# FEU.net
KiCad netlist of a schematic drawn in EAGLE
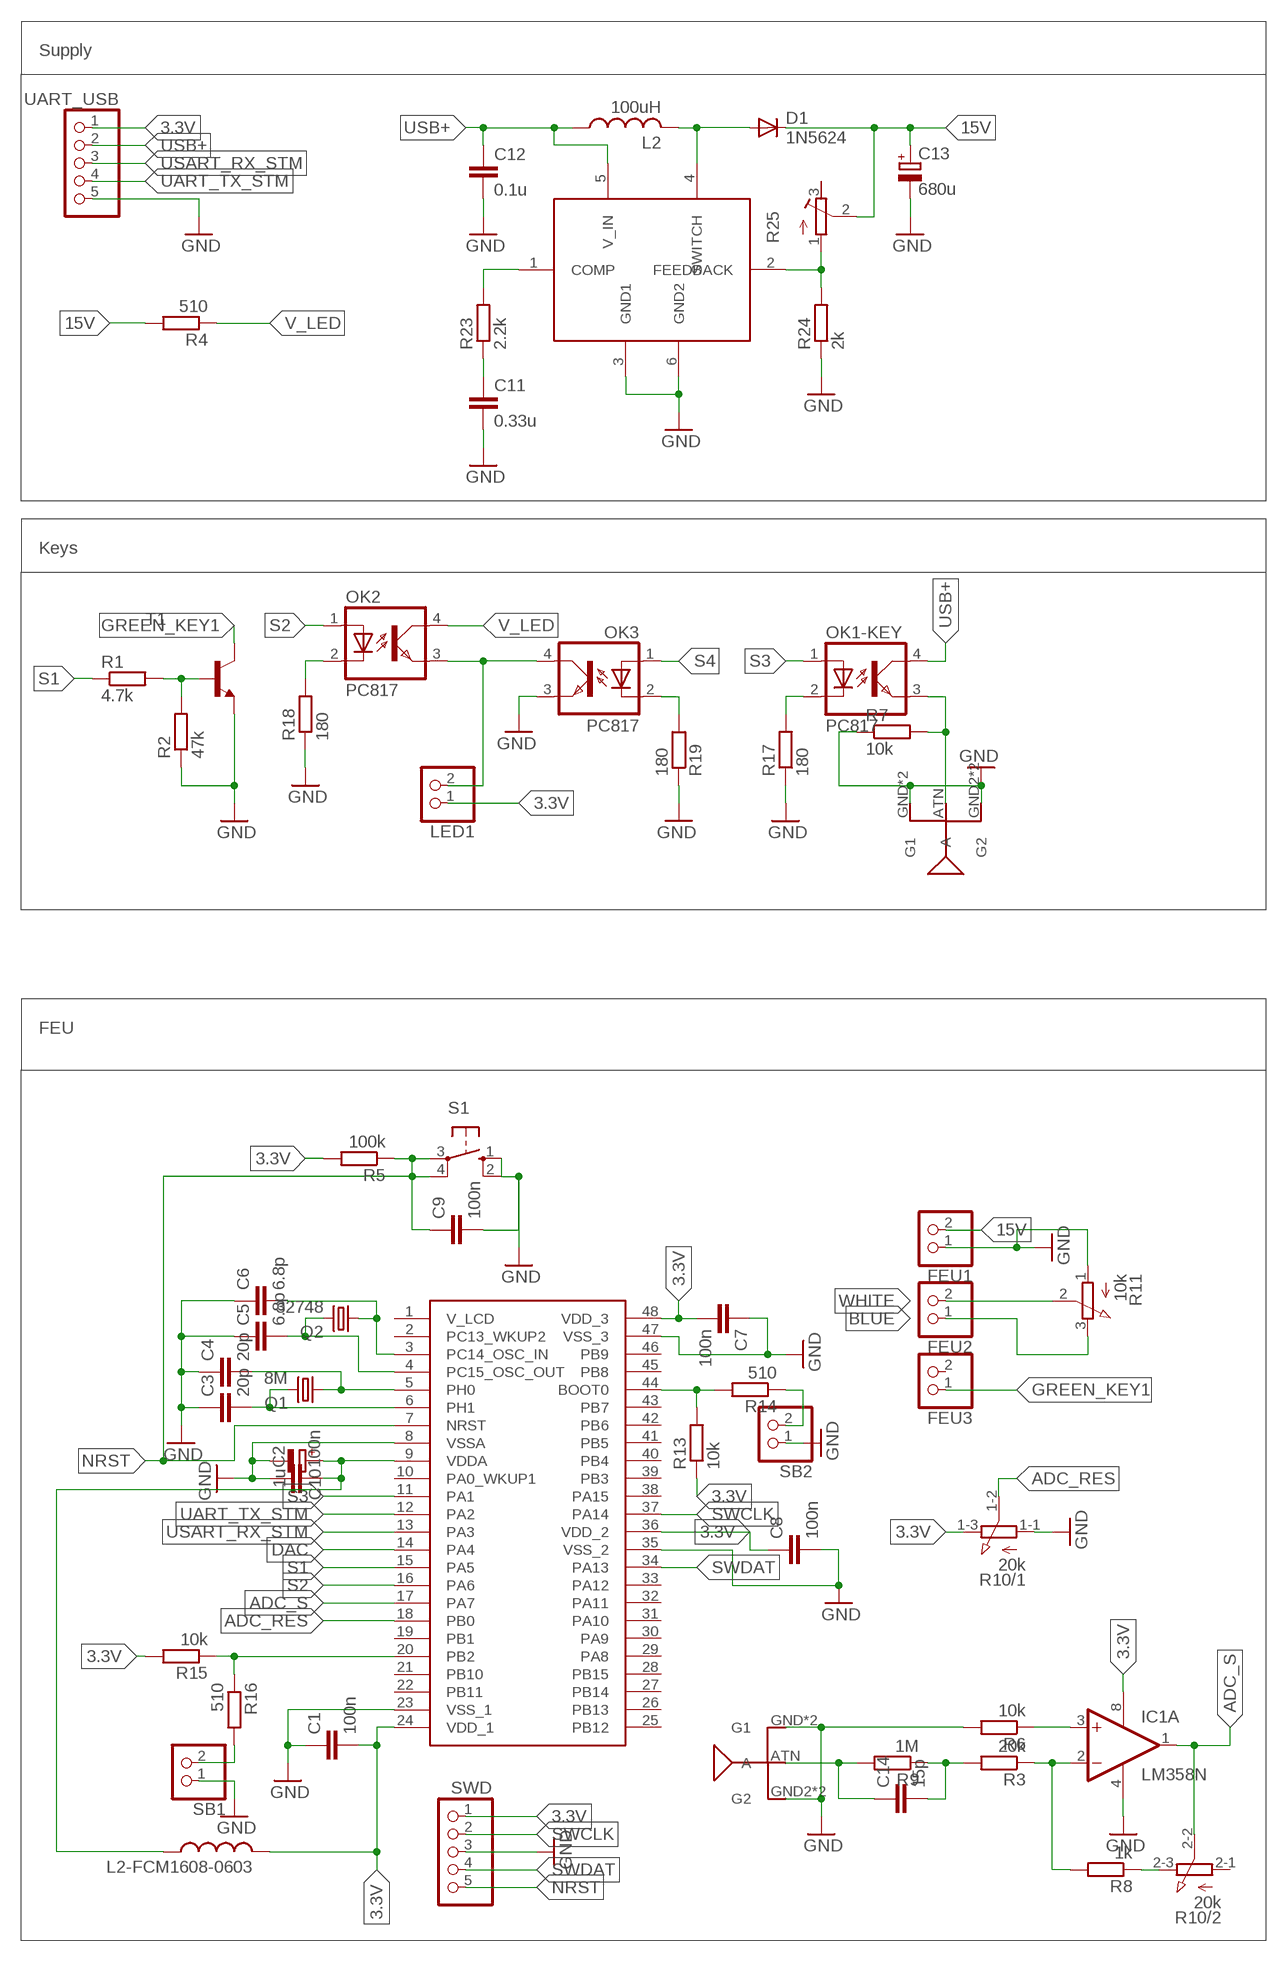
[diagram p0: schematic, sheet 1]

(export (version "E")
  (design (tool "Eeschema 10.0.6"))
  (components
    (comp (ref "C1")
      (value "100n")
      (footprint "eagle-import:C0805")
      (libsource (lib "eagle-import") (part "C-EUC0805"))
    )
    (comp (ref "C2")
      (value "100n")
      (footprint "eagle-import:C0805")
      (libsource (lib "eagle-import") (part "C-EUC0805"))
    )
    (comp (ref "C3")
      (value "20p")
      (footprint "eagle-import:C0805")
      (libsource (lib "eagle-import") (part "C-EUC0805"))
    )
    (comp (ref "C4")
      (value "20p")
      (footprint "eagle-import:C0805")
      (libsource (lib "eagle-import") (part "C-EUC0805"))
    )
    (comp (ref "C5")
      (value "6.8p")
      (footprint "eagle-import:C0805")
      (libsource (lib "eagle-import") (part "C-EUC0805"))
    )
    (comp (ref "C6")
      (value "6.8p")
      (footprint "eagle-import:C0805")
      (libsource (lib "eagle-import") (part "C-EUC0805"))
    )
    (comp (ref "C7")
      (value "100n")
      (footprint "eagle-import:C0805")
      (libsource (lib "eagle-import") (part "C-EUC0805"))
    )
    (comp (ref "C8")
      (value "100n")
      (footprint "eagle-import:C0805")
      (libsource (lib "eagle-import") (part "C-EUC0805"))
    )
    (comp (ref "C9")
      (value "100n")
      (footprint "eagle-import:C0805")
      (libsource (lib "eagle-import") (part "C-EUC0805"))
    )
    (comp (ref "C10")
      (value "1u")
      (footprint "eagle-import:A_3216-18W")
      (libsource (lib "eagle-import") (part "CPOL-EUA/3216-18W"))
    )
    (comp (ref "C11")
      (value "0.33u")
      (footprint "eagle-import:C0805")
      (libsource (lib "eagle-import") (part "C-EUC0805"))
    )
    (comp (ref "C12")
      (value "0.1u")
      (footprint "eagle-import:C0805")
      (libsource (lib "eagle-import") (part "C-EUC0805"))
    )
    (comp (ref "C13")
      (value "680u")
      (footprint "eagle-import:E5-5")
      (libsource (lib "eagle-import") (part "CPOL-EUE5-5"))
    )
    (comp (ref "C14")
      (value "15p")
      (footprint "eagle-import:C0805")
      (libsource (lib "eagle-import") (part "C-EUC0805"))
    )
    (comp (ref "D1")
      (value "1N5624")
      (footprint "eagle-import:DO201-15")
      (libsource (lib "eagle-import") (part "1N5624"))
    )
    (comp (ref "FEU1")
      (value "PINHD-1X2")
      (footprint "eagle-import:1X02")
      (libsource (lib "eagle-import") (part "PINHD-1X2"))
    )
    (comp (ref "FEU2")
      (value "PINHD-1X2")
      (footprint "eagle-import:1X02")
      (libsource (lib "eagle-import") (part "PINHD-1X2"))
    )
    (comp (ref "FEU3")
      (value "PINHD-1X2")
      (footprint "eagle-import:1X02")
      (libsource (lib "eagle-import") (part "PINHD-1X2"))
    )
    (comp (ref "IC1")
      (value "LM358N")
      (footprint "eagle-import:DIL08")
      (libsource (lib "eagle-import") (part "LM358N"))
    )
    (comp (ref "L2")
      (value "100uH")
      (footprint "eagle-import:0207_5V")
      (libsource (lib "eagle-import") (part "L-US0207/5V"))
    )
    (comp (ref "L2-FCM1608-0603")
      (value "L-USL3216C")
      (footprint "eagle-import:L3216C")
      (libsource (lib "eagle-import") (part "L-USL3216C"))
    )
    (comp (ref "LED1")
      (value "PINHD-1X2")
      (footprint "eagle-import:1X02")
      (libsource (lib "eagle-import") (part "PINHD-1X2"))
    )
    (comp (ref "OK1-KEY")
      (value "PC817")
      (footprint "eagle-import:DIL04")
      (fields (field (name "MPN") "PC817X4J000F"))
      (libsource (lib "eagle-import") (part "PC817"))
    )
    (comp (ref "OK2")
      (value "PC817")
      (footprint "eagle-import:DIL04")
      (fields (field (name "MPN") "PC817X4J000F"))
      (libsource (lib "eagle-import") (part "PC817"))
    )
    (comp (ref "OK3")
      (value "PC817")
      (footprint "eagle-import:DIL04")
      (fields (field (name "MPN") "PC817X4J000F"))
      (libsource (lib "eagle-import") (part "PC817"))
    )
    (comp (ref "Q1")
      (value "8M")
      (footprint "eagle-import:HC49_S")
      (fields (field (name "OC_FARNELL") "1667008"))
      (libsource (lib "eagle-import") (part "CRYSTALHC49S"))
    )
    (comp (ref "Q2")
      (value "32748")
      (footprint "eagle-import:TC26H")
      (libsource (lib "eagle-import") (part "CRYSTALTC26H"))
    )
    (comp (ref "R1")
      (value "4.7k")
      (footprint "eagle-import:R0805")
      (libsource (lib "eagle-import") (part "R-EU_R0805"))
    )
    (comp (ref "R2")
      (value "47k")
      (footprint "eagle-import:R0805")
      (libsource (lib "eagle-import") (part "R-EU_R0805"))
    )
    (comp (ref "R3")
      (value "20k")
      (footprint "eagle-import:M1206")
      (libsource (lib "eagle-import") (part "R-EU_M1206"))
    )
    (comp (ref "R4")
      (value "510")
      (footprint "eagle-import:R0805")
      (libsource (lib "eagle-import") (part "R-EU_R0805"))
    )
    (comp (ref "R5")
      (value "100k")
      (footprint "eagle-import:R0805")
      (libsource (lib "eagle-import") (part "R-EU_R0805"))
    )
    (comp (ref "R6")
      (value "10k")
      (footprint "eagle-import:M1206")
      (libsource (lib "eagle-import") (part "R-EU_M1206"))
    )
    (comp (ref "R7")
      (value "10k")
      (footprint "eagle-import:R0805")
      (libsource (lib "eagle-import") (part "R-EU_R0805"))
    )
    (comp (ref "R8")
      (value "1k")
      (footprint "eagle-import:M1206")
      (libsource (lib "eagle-import") (part "R-EU_M1206"))
    )
    (comp (ref "R9")
      (value "1M")
      (footprint "eagle-import:M1206")
      (libsource (lib "eagle-import") (part "R-EU_M1206"))
    )
    (comp (ref "R10")
      (value "20k")
      (footprint "eagle-import:3RP_1610G")
      (libsource (lib "eagle-import") (part "3RP/1610G"))
    )
    (comp (ref "R11")
      (value "10k")
      (footprint "eagle-import:3RP_1610N")
      (libsource (lib "eagle-import") (part "3RP/1610N"))
    )
    (comp (ref "R13")
      (value "10k")
      (footprint "eagle-import:R0805")
      (libsource (lib "eagle-import") (part "R-EU_R0805"))
    )
    (comp (ref "R14")
      (value "510")
      (footprint "eagle-import:R0805")
      (libsource (lib "eagle-import") (part "R-EU_R0805"))
    )
    (comp (ref "R15")
      (value "10k")
      (footprint "eagle-import:R0805")
      (libsource (lib "eagle-import") (part "R-EU_R0805"))
    )
    (comp (ref "R16")
      (value "510")
      (footprint "eagle-import:R0805")
      (libsource (lib "eagle-import") (part "R-EU_R0805"))
    )
    (comp (ref "R17")
      (value "180")
      (footprint "eagle-import:R0805")
      (libsource (lib "eagle-import") (part "R-EU_R0805"))
    )
    (comp (ref "R18")
      (value "180")
      (footprint "eagle-import:R0805")
      (libsource (lib "eagle-import") (part "R-EU_R0805"))
    )
    (comp (ref "R19")
      (value "180")
      (footprint "eagle-import:R0805")
      (libsource (lib "eagle-import") (part "R-EU_R0805"))
    )
    (comp (ref "R23")
      (value "2.2k")
      (footprint "eagle-import:R0805")
      (libsource (lib "eagle-import") (part "R-EU_R0805"))
    )
    (comp (ref "R24")
      (value "2k")
      (footprint "eagle-import:R0805")
      (libsource (lib "eagle-import") (part "R-EU_R0805"))
    )
    (comp (ref "R25")
      (value "R-TRIMM3339P")
      (footprint "eagle-import:RTRIM3339P")
      (libsource (lib "eagle-import") (part "R-TRIMM3339P"))
    )
    (comp (ref "S1")
      (value "10-XX")
      (footprint "eagle-import:B3F-10XX")
      (fields (field (name "MPN") "B3F-1000"))
      (libsource (lib "eagle-import") (part "10-XX"))
    )
    (comp (ref "SB1")
      (value "PINHD-1X2")
      (footprint "eagle-import:1X02")
      (libsource (lib "eagle-import") (part "PINHD-1X2"))
    )
    (comp (ref "SB2")
      (value "PINHD-1X2")
      (footprint "eagle-import:1X02")
      (libsource (lib "eagle-import") (part "PINHD-1X2"))
    )
    (comp (ref "SWD")
      (value "PINHD-1X5")
      (footprint "eagle-import:1X05")
      (libsource (lib "eagle-import") (part "PINHD-1X5"))
    )
    (comp (ref "T1")
      (value "BC846B-NPN-SOT23-BEC")
      (footprint "eagle-import:SOT23-BEC")
      (libsource (lib "eagle-import") (part "-NPN-SOT23-BECBC846B"))
    )
    (comp (ref "U$1")
      (value "STM32L152C6")
      (footprint "eagle-import:LQFP48")
      (libsource (lib "eagle-import") (part "STM32L152C6"))
    )
    (comp (ref "U$2")
      (value "GSM_ANT")
      (footprint "eagle-import:GSM")
      (libsource (lib "eagle-import") (part "GSM_ANT"))
    )
    (comp (ref "U$3")
      (value "GSM_ANT")
      (footprint "eagle-import:GSM")
      (libsource (lib "eagle-import") (part "GSM_ANT"))
    )
    (comp (ref "U$4")
      (value "LM2577")
      (footprint "eagle-import:TO263-5")
      (libsource (lib "eagle-import") (part "LM2577"))
    )
    (comp (ref "UART_USB")
      (value "PINHD-1X5")
      (footprint "eagle-import:1X05")
      (libsource (lib "eagle-import") (part "PINHD-1X5"))
    )
  )
  (nets
    (net (code "1") (name "3.3V") (class "Default")
      (node (ref "C1") (pin "2") (pinfunction "2_2") (pintype "passive"))
      (node (ref "C7") (pin "2") (pinfunction "2_2") (pintype "passive"))
      (node (ref "C8") (pin "1") (pinfunction "1_1") (pintype "passive"))
      (node (ref "IC1") (pin "8") (pinfunction "V+_8") (pintype "power_in"))
      (node (ref "L2-FCM1608-0603") (pin "2") (pinfunction "2_2") (pintype "passive"))
      (node (ref "LED1") (pin "1") (pinfunction "1_1") (pintype "passive"))
      (node (ref "R10") (pin "1-3") (pinfunction "E_1-3") (pintype "passive"))
      (node (ref "R13") (pin "1") (pinfunction "1_1") (pintype "passive"))
      (node (ref "R15") (pin "2") (pinfunction "2_2") (pintype "passive"))
      (node (ref "R5") (pin "2") (pinfunction "2_2") (pintype "passive"))
      (node (ref "SWD") (pin "1") (pinfunction "1_1") (pintype "passive"))
      (node (ref "U$1") (pin "24") (pinfunction "VDD_1_24") (pintype "bidirectional"))
      (node (ref "U$1") (pin "36") (pinfunction "VDD_2_36") (pintype "bidirectional"))
      (node (ref "U$1") (pin "48") (pinfunction "VDD_3_48") (pintype "bidirectional"))
      (node (ref "UART_USB") (pin "1") (pinfunction "1_1") (pintype "passive"))
    )
    (net (code "2") (name "15V") (class "Default")
      (node (ref "C13") (pin "+") (pinfunction "+_+") (pintype "passive"))
      (node (ref "D1") (pin "C") (pinfunction "C_C") (pintype "passive"))
      (node (ref "FEU1") (pin "2") (pinfunction "2_2") (pintype "passive"))
      (node (ref "R25") (pin "2") (pinfunction "S_2") (pintype "passive"))
      (node (ref "R4") (pin "2") (pinfunction "2_2") (pintype "passive"))
    )
    (net (code "3") (name "ADC_RES") (class "Default")
      (node (ref "R10") (pin "1-2") (pinfunction "S_1-2") (pintype "passive"))
      (node (ref "U$1") (pin "18") (pinfunction "PB0_18") (pintype "bidirectional"))
    )
    (net (code "4") (name "ADC_S") (class "Default")
      (node (ref "IC1") (pin "1") (pinfunction "OUT_1") (pintype "output"))
      (node (ref "R10") (pin "2-2") (pinfunction "S_2-2") (pintype "passive"))
      (node (ref "U$1") (pin "17") (pinfunction "PA7_17") (pintype "bidirectional"))
    )
    (net (code "5") (name "BLUE") (class "Default")
      (node (ref "FEU2") (pin "1") (pinfunction "1_1") (pintype "passive"))
      (node (ref "R11") (pin "3") (pinfunction "E_3") (pintype "passive"))
    )
    (net (code "6") (name "DAC") (class "Default")
      (node (ref "U$1") (pin "14") (pinfunction "PA4_14") (pintype "bidirectional"))
    )
    (net (code "7") (name "GND") (class "Default")
      (node (ref "C1") (pin "1") (pinfunction "1_1") (pintype "passive"))
      (node (ref "C10") (pin "-") (pinfunction "-_-") (pintype "passive"))
      (node (ref "C11") (pin "2") (pinfunction "2_2") (pintype "passive"))
      (node (ref "C12") (pin "2") (pinfunction "2_2") (pintype "passive"))
      (node (ref "C13") (pin "-") (pinfunction "-_-") (pintype "passive"))
      (node (ref "C2") (pin "1") (pinfunction "1_1") (pintype "passive"))
      (node (ref "C3") (pin "1") (pinfunction "1_1") (pintype "passive"))
      (node (ref "C4") (pin "1") (pinfunction "1_1") (pintype "passive"))
      (node (ref "C5") (pin "1") (pinfunction "1_1") (pintype "passive"))
      (node (ref "C6") (pin "1") (pinfunction "1_1") (pintype "passive"))
      (node (ref "C7") (pin "1") (pinfunction "1_1") (pintype "passive"))
      (node (ref "C8") (pin "2") (pinfunction "2_2") (pintype "passive"))
      (node (ref "C9") (pin "2") (pinfunction "2_2") (pintype "passive"))
      (node (ref "FEU1") (pin "1") (pinfunction "1_1") (pintype "passive"))
      (node (ref "IC1") (pin "4") (pinfunction "V-_4") (pintype "power_in"))
      (node (ref "OK3") (pin "3") (pinfunction "EMIT_3") (pintype "passive"))
      (node (ref "R10") (pin "1-1") (pinfunction "A_1-1") (pintype "passive"))
      (node (ref "R11") (pin "1") (pinfunction "A_1") (pintype "passive"))
      (node (ref "R17") (pin "1") (pinfunction "1_1") (pintype "passive"))
      (node (ref "R18") (pin "1") (pinfunction "1_1") (pintype "passive"))
      (node (ref "R19") (pin "1") (pinfunction "1_1") (pintype "passive"))
      (node (ref "R2") (pin "1") (pinfunction "1_1") (pintype "passive"))
      (node (ref "R24") (pin "1") (pinfunction "1_1") (pintype "passive"))
      (node (ref "R6") (pin "2") (pinfunction "2_2") (pintype "passive"))
      (node (ref "R7") (pin "1") (pinfunction "1_1") (pintype "passive"))
      (node (ref "S1") (pin "1") (pinfunction "S_1") (pintype "passive"))
      (node (ref "S1") (pin "2") (pinfunction "S1_2") (pintype "passive"))
      (node (ref "SB1") (pin "1") (pinfunction "1_1") (pintype "passive"))
      (node (ref "SB2") (pin "1") (pinfunction "1_1") (pintype "passive"))
      (node (ref "SWD") (pin "3") (pinfunction "3_3") (pintype "passive"))
      (node (ref "T1") (pin "E") (pinfunction "E_E") (pintype "passive"))
      (node (ref "U$1") (pin "23") (pinfunction "VSS_1_23") (pintype "bidirectional"))
      (node (ref "U$1") (pin "35") (pinfunction "VSS_2_35") (pintype "bidirectional"))
      (node (ref "U$1") (pin "47") (pinfunction "VSS_3_47") (pintype "bidirectional"))
      (node (ref "U$1") (pin "8") (pinfunction "VSSA_8") (pintype "bidirectional"))
      (node (ref "U$2") (pin "GND") (pinfunction "G1_GND") (pintype "bidirectional"))
      (node (ref "U$2") (pin "GND1") (pinfunction "G1_GND1") (pintype "bidirectional"))
      (node (ref "U$2") (pin "GND2") (pinfunction "G2_GND2") (pintype "bidirectional"))
      (node (ref "U$2") (pin "GND3") (pinfunction "G2_GND3") (pintype "bidirectional"))
      (node (ref "U$3") (pin "GND") (pinfunction "G1_GND") (pintype "bidirectional"))
      (node (ref "U$3") (pin "GND1") (pinfunction "G1_GND1") (pintype "bidirectional"))
      (node (ref "U$3") (pin "GND2") (pinfunction "G2_GND2") (pintype "bidirectional"))
      (node (ref "U$3") (pin "GND3") (pinfunction "G2_GND3") (pintype "bidirectional"))
      (node (ref "U$4") (pin "3") (pinfunction "GND1_3") (pintype "bidirectional"))
      (node (ref "U$4") (pin "6") (pinfunction "GND2_6") (pintype "bidirectional"))
      (node (ref "UART_USB") (pin "5") (pinfunction "5_5") (pintype "passive"))
    )
    (net (code "8") (name "GREEN_KEY1") (class "Default")
      (node (ref "FEU3") (pin "1") (pinfunction "1_1") (pintype "passive"))
      (node (ref "T1") (pin "C") (pinfunction "C_C") (pintype "passive"))
    )
    (net (code "9") (name "NRST") (class "Default")
      (node (ref "C9") (pin "1") (pinfunction "1_1") (pintype "passive"))
      (node (ref "R5") (pin "1") (pinfunction "1_1") (pintype "passive"))
      (node (ref "S1") (pin "3") (pinfunction "P_3") (pintype "passive"))
      (node (ref "S1") (pin "4") (pinfunction "P1_4") (pintype "passive"))
      (node (ref "SWD") (pin "5") (pinfunction "5_5") (pintype "passive"))
      (node (ref "U$1") (pin "7") (pinfunction "NRST_7") (pintype "bidirectional"))
    )
    (net (code "10") (name "Net-(C11-Pad1)") (class "Default")
      (node (ref "C11") (pin "1") (pinfunction "1_1") (pintype "passive"))
      (node (ref "R23") (pin "1") (pinfunction "1_1") (pintype "passive"))
    )
    (net (code "11") (name "Net-(C14-Pad2)") (class "Default")
      (node (ref "C14") (pin "2") (pinfunction "2_2") (pintype "passive"))
      (node (ref "R3") (pin "2") (pinfunction "2_2") (pintype "passive"))
      (node (ref "R9") (pin "1") (pinfunction "1_1") (pintype "passive"))
    )
    (net (code "12") (name "Net-(IC1A-+IN)") (class "Default")
      (node (ref "IC1") (pin "3") (pinfunction "+IN_3") (pintype "input"))
      (node (ref "R6") (pin "1") (pinfunction "1_1") (pintype "passive"))
    )
    (net (code "13") (name "Net-(IC1A--IN)") (class "Default")
      (node (ref "IC1") (pin "2") (pinfunction "-IN_2") (pintype "input"))
      (node (ref "R3") (pin "1") (pinfunction "1_1") (pintype "passive"))
      (node (ref "R8") (pin "2") (pinfunction "2_2") (pintype "passive"))
    )
    (net (code "14") (name "Net-(OK1-KEY-C)") (class "Default")
      (node (ref "OK1-KEY") (pin "2") (pinfunction "C_2") (pintype "passive"))
      (node (ref "R17") (pin "2") (pinfunction "2_2") (pintype "passive"))
    )
    (net (code "15") (name "Net-(OK1-KEY-EMIT)") (class "Default")
      (node (ref "OK1-KEY") (pin "3") (pinfunction "EMIT_3") (pintype "passive"))
      (node (ref "R7") (pin "2") (pinfunction "2_2") (pintype "passive"))
      (node (ref "U$3") (pin "ATN") (pinfunction "A_ATN") (pintype "bidirectional"))
    )
    (net (code "16") (name "Net-(OK2-C)") (class "Default")
      (node (ref "OK2") (pin "2") (pinfunction "C_2") (pintype "passive"))
      (node (ref "R18") (pin "2") (pinfunction "2_2") (pintype "passive"))
    )
    (net (code "17") (name "Net-(OK2-EMIT)") (class "Default")
      (node (ref "LED1") (pin "2") (pinfunction "2_2") (pintype "passive"))
      (node (ref "OK2") (pin "3") (pinfunction "EMIT_3") (pintype "passive"))
      (node (ref "OK3") (pin "4") (pinfunction "COL_4") (pintype "passive"))
    )
    (net (code "18") (name "Net-(OK3-C)") (class "Default")
      (node (ref "OK3") (pin "2") (pinfunction "C_2") (pintype "passive"))
      (node (ref "R19") (pin "2") (pinfunction "2_2") (pintype "passive"))
    )
    (net (code "19") (name "Net-(R1-Pad2)") (class "Default")
      (node (ref "R1") (pin "2") (pinfunction "2_2") (pintype "passive"))
      (node (ref "R2") (pin "2") (pinfunction "2_2") (pintype "passive"))
      (node (ref "T1") (pin "B") (pinfunction "B_B") (pintype "passive"))
    )
    (net (code "20") (name "Net-(R10B-E)") (class "Default")
      (node (ref "R10") (pin "2-3") (pinfunction "E_2-3") (pintype "passive"))
      (node (ref "R8") (pin "1") (pinfunction "1_1") (pintype "passive"))
    )
    (net (code "21") (name "Net-(R14-Pad1)") (class "Default")
      (node (ref "R14") (pin "1") (pinfunction "1_1") (pintype "passive"))
      (node (ref "SB2") (pin "2") (pinfunction "2_2") (pintype "passive"))
    )
    (net (code "22") (name "Net-(R16-Pad2)") (class "Default")
      (node (ref "R16") (pin "2") (pinfunction "2_2") (pintype "passive"))
      (node (ref "SB1") (pin "2") (pinfunction "2_2") (pintype "passive"))
    )
    (net (code "23") (name "Net-(R25-E)") (class "Default")
      (node (ref "R24") (pin "2") (pinfunction "2_2") (pintype "passive"))
      (node (ref "R25") (pin "1") (pinfunction "E_1") (pintype "passive"))
      (node (ref "U$4") (pin "2") (pinfunction "FEEDBACK_2") (pintype "bidirectional"))
    )
    (net (code "24") (name "Net-(U$1-BOOT0)") (class "Default")
      (node (ref "R13") (pin "2") (pinfunction "2_2") (pintype "passive"))
      (node (ref "R14") (pin "2") (pinfunction "2_2") (pintype "passive"))
      (node (ref "U$1") (pin "44") (pinfunction "BOOT0_44") (pintype "bidirectional"))
    )
    (net (code "25") (name "Net-(U$1-PB2)") (class "Default")
      (node (ref "R15") (pin "1") (pinfunction "1_1") (pintype "passive"))
      (node (ref "R16") (pin "1") (pinfunction "1_1") (pintype "passive"))
      (node (ref "U$1") (pin "20") (pinfunction "PB2_20") (pintype "bidirectional"))
    )
    (net (code "26") (name "Net-(U$1-PC14_OSC_IN)") (class "Default")
      (node (ref "C6") (pin "2") (pinfunction "2_2") (pintype "passive"))
      (node (ref "Q2") (pin "1") (pinfunction "1_1") (pintype "passive"))
      (node (ref "U$1") (pin "3") (pinfunction "PC14_OSC_IN_3") (pintype "bidirectional"))
    )
    (net (code "27") (name "Net-(U$1-PC15_OSC_OUT)") (class "Default")
      (node (ref "C5") (pin "2") (pinfunction "2_2") (pintype "passive"))
      (node (ref "Q2") (pin "2") (pinfunction "2_2") (pintype "passive"))
      (node (ref "U$1") (pin "4") (pinfunction "PC15_OSC_OUT_4") (pintype "bidirectional"))
    )
    (net (code "28") (name "Net-(U$1-PH0)") (class "Default")
      (node (ref "C4") (pin "2") (pinfunction "2_2") (pintype "passive"))
      (node (ref "Q1") (pin "1") (pinfunction "1_1") (pintype "passive"))
      (node (ref "U$1") (pin "5") (pinfunction "PH0_5") (pintype "bidirectional"))
    )
    (net (code "29") (name "Net-(U$1-PH1)") (class "Default")
      (node (ref "C3") (pin "2") (pinfunction "2_2") (pintype "passive"))
      (node (ref "Q1") (pin "2") (pinfunction "2_2") (pintype "passive"))
      (node (ref "U$1") (pin "6") (pinfunction "PH1_6") (pintype "bidirectional"))
    )
    (net (code "30") (name "Net-(U$1-VDDA)") (class "Default")
      (node (ref "C10") (pin "+") (pinfunction "+_+") (pintype "passive"))
      (node (ref "C2") (pin "2") (pinfunction "2_2") (pintype "passive"))
      (node (ref "L2-FCM1608-0603") (pin "1") (pinfunction "1_1") (pintype "passive"))
      (node (ref "U$1") (pin "9") (pinfunction "VDDA_9") (pintype "bidirectional"))
    )
    (net (code "31") (name "Net-(U$2-A)") (class "Default")
      (node (ref "C14") (pin "1") (pinfunction "1_1") (pintype "passive"))
      (node (ref "R9") (pin "2") (pinfunction "2_2") (pintype "passive"))
      (node (ref "U$2") (pin "ATN") (pinfunction "A_ATN") (pintype "bidirectional"))
    )
    (net (code "32") (name "Net-(U$4-COMP)") (class "Default")
      (node (ref "R23") (pin "2") (pinfunction "2_2") (pintype "passive"))
      (node (ref "U$4") (pin "1") (pinfunction "COMP_1") (pintype "bidirectional"))
    )
    (net (code "33") (name "Net-(U$4-SWITCH)") (class "Default")
      (node (ref "D1") (pin "A") (pinfunction "A_A") (pintype "passive"))
      (node (ref "L2") (pin "2") (pinfunction "2_2") (pintype "passive"))
      (node (ref "U$4") (pin "4") (pinfunction "SWITCH_4") (pintype "bidirectional"))
    )
    (net (code "34") (name "S1") (class "Default")
      (node (ref "R1") (pin "1") (pinfunction "1_1") (pintype "passive"))
      (node (ref "U$1") (pin "15") (pinfunction "PA5_15") (pintype "bidirectional"))
    )
    (net (code "35") (name "S2") (class "Default")
      (node (ref "OK2") (pin "1") (pinfunction "A_1") (pintype "passive"))
      (node (ref "U$1") (pin "16") (pinfunction "PA6_16") (pintype "bidirectional"))
    )
    (net (code "36") (name "S3") (class "Default")
      (node (ref "OK1-KEY") (pin "1") (pinfunction "A_1") (pintype "passive"))
      (node (ref "U$1") (pin "11") (pinfunction "PA1_11") (pintype "bidirectional"))
    )
    (net (code "37") (name "S4") (class "Default")
      (node (ref "OK3") (pin "1") (pinfunction "A_1") (pintype "passive"))
    )
    (net (code "38") (name "SWCLK") (class "Default")
      (node (ref "SWD") (pin "2") (pinfunction "2_2") (pintype "passive"))
      (node (ref "U$1") (pin "37") (pinfunction "PA14_37") (pintype "bidirectional"))
    )
    (net (code "39") (name "SWDAT") (class "Default")
      (node (ref "SWD") (pin "4") (pinfunction "4_4") (pintype "passive"))
      (node (ref "U$1") (pin "34") (pinfunction "PA13_34") (pintype "bidirectional"))
    )
    (net (code "40") (name "UART_TX_STM") (class "Default")
      (node (ref "U$1") (pin "12") (pinfunction "PA2_12") (pintype "bidirectional"))
      (node (ref "UART_USB") (pin "4") (pinfunction "4_4") (pintype "passive"))
    )
    (net (code "41") (name "USART_RX_STM") (class "Default")
      (node (ref "U$1") (pin "13") (pinfunction "PA3_13") (pintype "bidirectional"))
      (node (ref "UART_USB") (pin "3") (pinfunction "3_3") (pintype "passive"))
    )
    (net (code "42") (name "USB+") (class "Default")
      (node (ref "C12") (pin "1") (pinfunction "1_1") (pintype "passive"))
      (node (ref "L2") (pin "1") (pinfunction "1_1") (pintype "passive"))
      (node (ref "OK1-KEY") (pin "4") (pinfunction "COL_4") (pintype "passive"))
      (node (ref "U$4") (pin "5") (pinfunction "V_IN_5") (pintype "bidirectional"))
      (node (ref "UART_USB") (pin "2") (pinfunction "2_2") (pintype "passive"))
    )
    (net (code "43") (name "V_LED") (class "Default")
      (node (ref "OK2") (pin "4") (pinfunction "COL_4") (pintype "passive"))
      (node (ref "R4") (pin "1") (pinfunction "1_1") (pintype "passive"))
    )
    (net (code "44") (name "WHITE") (class "Default")
      (node (ref "FEU2") (pin "2") (pinfunction "2_2") (pintype "passive"))
      (node (ref "R11") (pin "2") (pinfunction "S_2") (pintype "passive"))
    )
    (net (code "45") (name "unconnected-(FEU3-Pad2)") (class "Default")
      (node (ref "FEU3") (pin "2") (pinfunction "2_2") (pintype "passive"))
    )
    (net (code "46") (name "unconnected-(R10B-A-Pad2-1)") (class "Default")
      (node (ref "R10") (pin "2-1") (pinfunction "A_2-1") (pintype "passive"))
    )
    (net (code "47") (name "unconnected-(R25-A-Pad3)") (class "Default")
      (node (ref "R25") (pin "3") (pinfunction "A_3") (pintype "passive"))
    )
    (net (code "48") (name "unconnected-(U$1-PA0_WKUP1-Pad10)") (class "Default")
      (node (ref "U$1") (pin "10") (pinfunction "PA0_WKUP1_10") (pintype "bidirectional"))
    )
    (net (code "49") (name "unconnected-(U$1-PA8-Pad29)") (class "Default")
      (node (ref "U$1") (pin "29") (pinfunction "PA8_29") (pintype "bidirectional"))
    )
    (net (code "50") (name "unconnected-(U$1-PA9-Pad30)") (class "Default")
      (node (ref "U$1") (pin "30") (pinfunction "PA9_30") (pintype "bidirectional"))
    )
    (net (code "51") (name "unconnected-(U$1-PA10-Pad31)") (class "Default")
      (node (ref "U$1") (pin "31") (pinfunction "PA10_31") (pintype "bidirectional"))
    )
    (net (code "52") (name "unconnected-(U$1-PA11-Pad32)") (class "Default")
      (node (ref "U$1") (pin "32") (pinfunction "PA11_32") (pintype "bidirectional"))
    )
    (net (code "53") (name "unconnected-(U$1-PA12-Pad33)") (class "Default")
      (node (ref "U$1") (pin "33") (pinfunction "PA12_33") (pintype "bidirectional"))
    )
    (net (code "54") (name "unconnected-(U$1-PA15-Pad38)") (class "Default")
      (node (ref "U$1") (pin "38") (pinfunction "PA15_38") (pintype "bidirectional"))
    )
    (net (code "55") (name "unconnected-(U$1-PB1-Pad19)") (class "Default")
      (node (ref "U$1") (pin "19") (pinfunction "PB1_19") (pintype "bidirectional"))
    )
    (net (code "56") (name "unconnected-(U$1-PB3-Pad39)") (class "Default")
      (node (ref "U$1") (pin "39") (pinfunction "PB3_39") (pintype "bidirectional"))
    )
    (net (code "57") (name "unconnected-(U$1-PB4-Pad40)") (class "Default")
      (node (ref "U$1") (pin "40") (pinfunction "PB4_40") (pintype "bidirectional"))
    )
    (net (code "58") (name "unconnected-(U$1-PB5-Pad41)") (class "Default")
      (node (ref "U$1") (pin "41") (pinfunction "PB5_41") (pintype "bidirectional"))
    )
    (net (code "59") (name "unconnected-(U$1-PB6-Pad42)") (class "Default")
      (node (ref "U$1") (pin "42") (pinfunction "PB6_42") (pintype "bidirectional"))
    )
    (net (code "60") (name "unconnected-(U$1-PB7-Pad43)") (class "Default")
      (node (ref "U$1") (pin "43") (pinfunction "PB7_43") (pintype "bidirectional"))
    )
    (net (code "61") (name "unconnected-(U$1-PB8-Pad45)") (class "Default")
      (node (ref "U$1") (pin "45") (pinfunction "PB8_45") (pintype "bidirectional"))
    )
    (net (code "62") (name "unconnected-(U$1-PB9-Pad46)") (class "Default")
      (node (ref "U$1") (pin "46") (pinfunction "PB9_46") (pintype "bidirectional"))
    )
    (net (code "63") (name "unconnected-(U$1-PB10-Pad21)") (class "Default")
      (node (ref "U$1") (pin "21") (pinfunction "PB10_21") (pintype "bidirectional"))
    )
    (net (code "64") (name "unconnected-(U$1-PB11-Pad22)") (class "Default")
      (node (ref "U$1") (pin "22") (pinfunction "PB11_22") (pintype "bidirectional"))
    )
    (net (code "65") (name "unconnected-(U$1-PB12-Pad25)") (class "Default")
      (node (ref "U$1") (pin "25") (pinfunction "PB12_25") (pintype "bidirectional"))
    )
    (net (code "66") (name "unconnected-(U$1-PB13-Pad26)") (class "Default")
      (node (ref "U$1") (pin "26") (pinfunction "PB13_26") (pintype "bidirectional"))
    )
    (net (code "67") (name "unconnected-(U$1-PB14-Pad27)") (class "Default")
      (node (ref "U$1") (pin "27") (pinfunction "PB14_27") (pintype "bidirectional"))
    )
    (net (code "68") (name "unconnected-(U$1-PB15-Pad28)") (class "Default")
      (node (ref "U$1") (pin "28") (pinfunction "PB15_28") (pintype "bidirectional"))
    )
    (net (code "69") (name "unconnected-(U$1-PC13_WKUP2-Pad2)") (class "Default")
      (node (ref "U$1") (pin "2") (pinfunction "PC13_WKUP2_2") (pintype "bidirectional"))
    )
    (net (code "70") (name "unconnected-(U$1-V_LCD-Pad1)") (class "Default")
      (node (ref "U$1") (pin "1") (pinfunction "V_LCD_1") (pintype "bidirectional"))
    )
  )
)
